# Car.net
KiCad netlist of a schematic drawn in Altium Designer
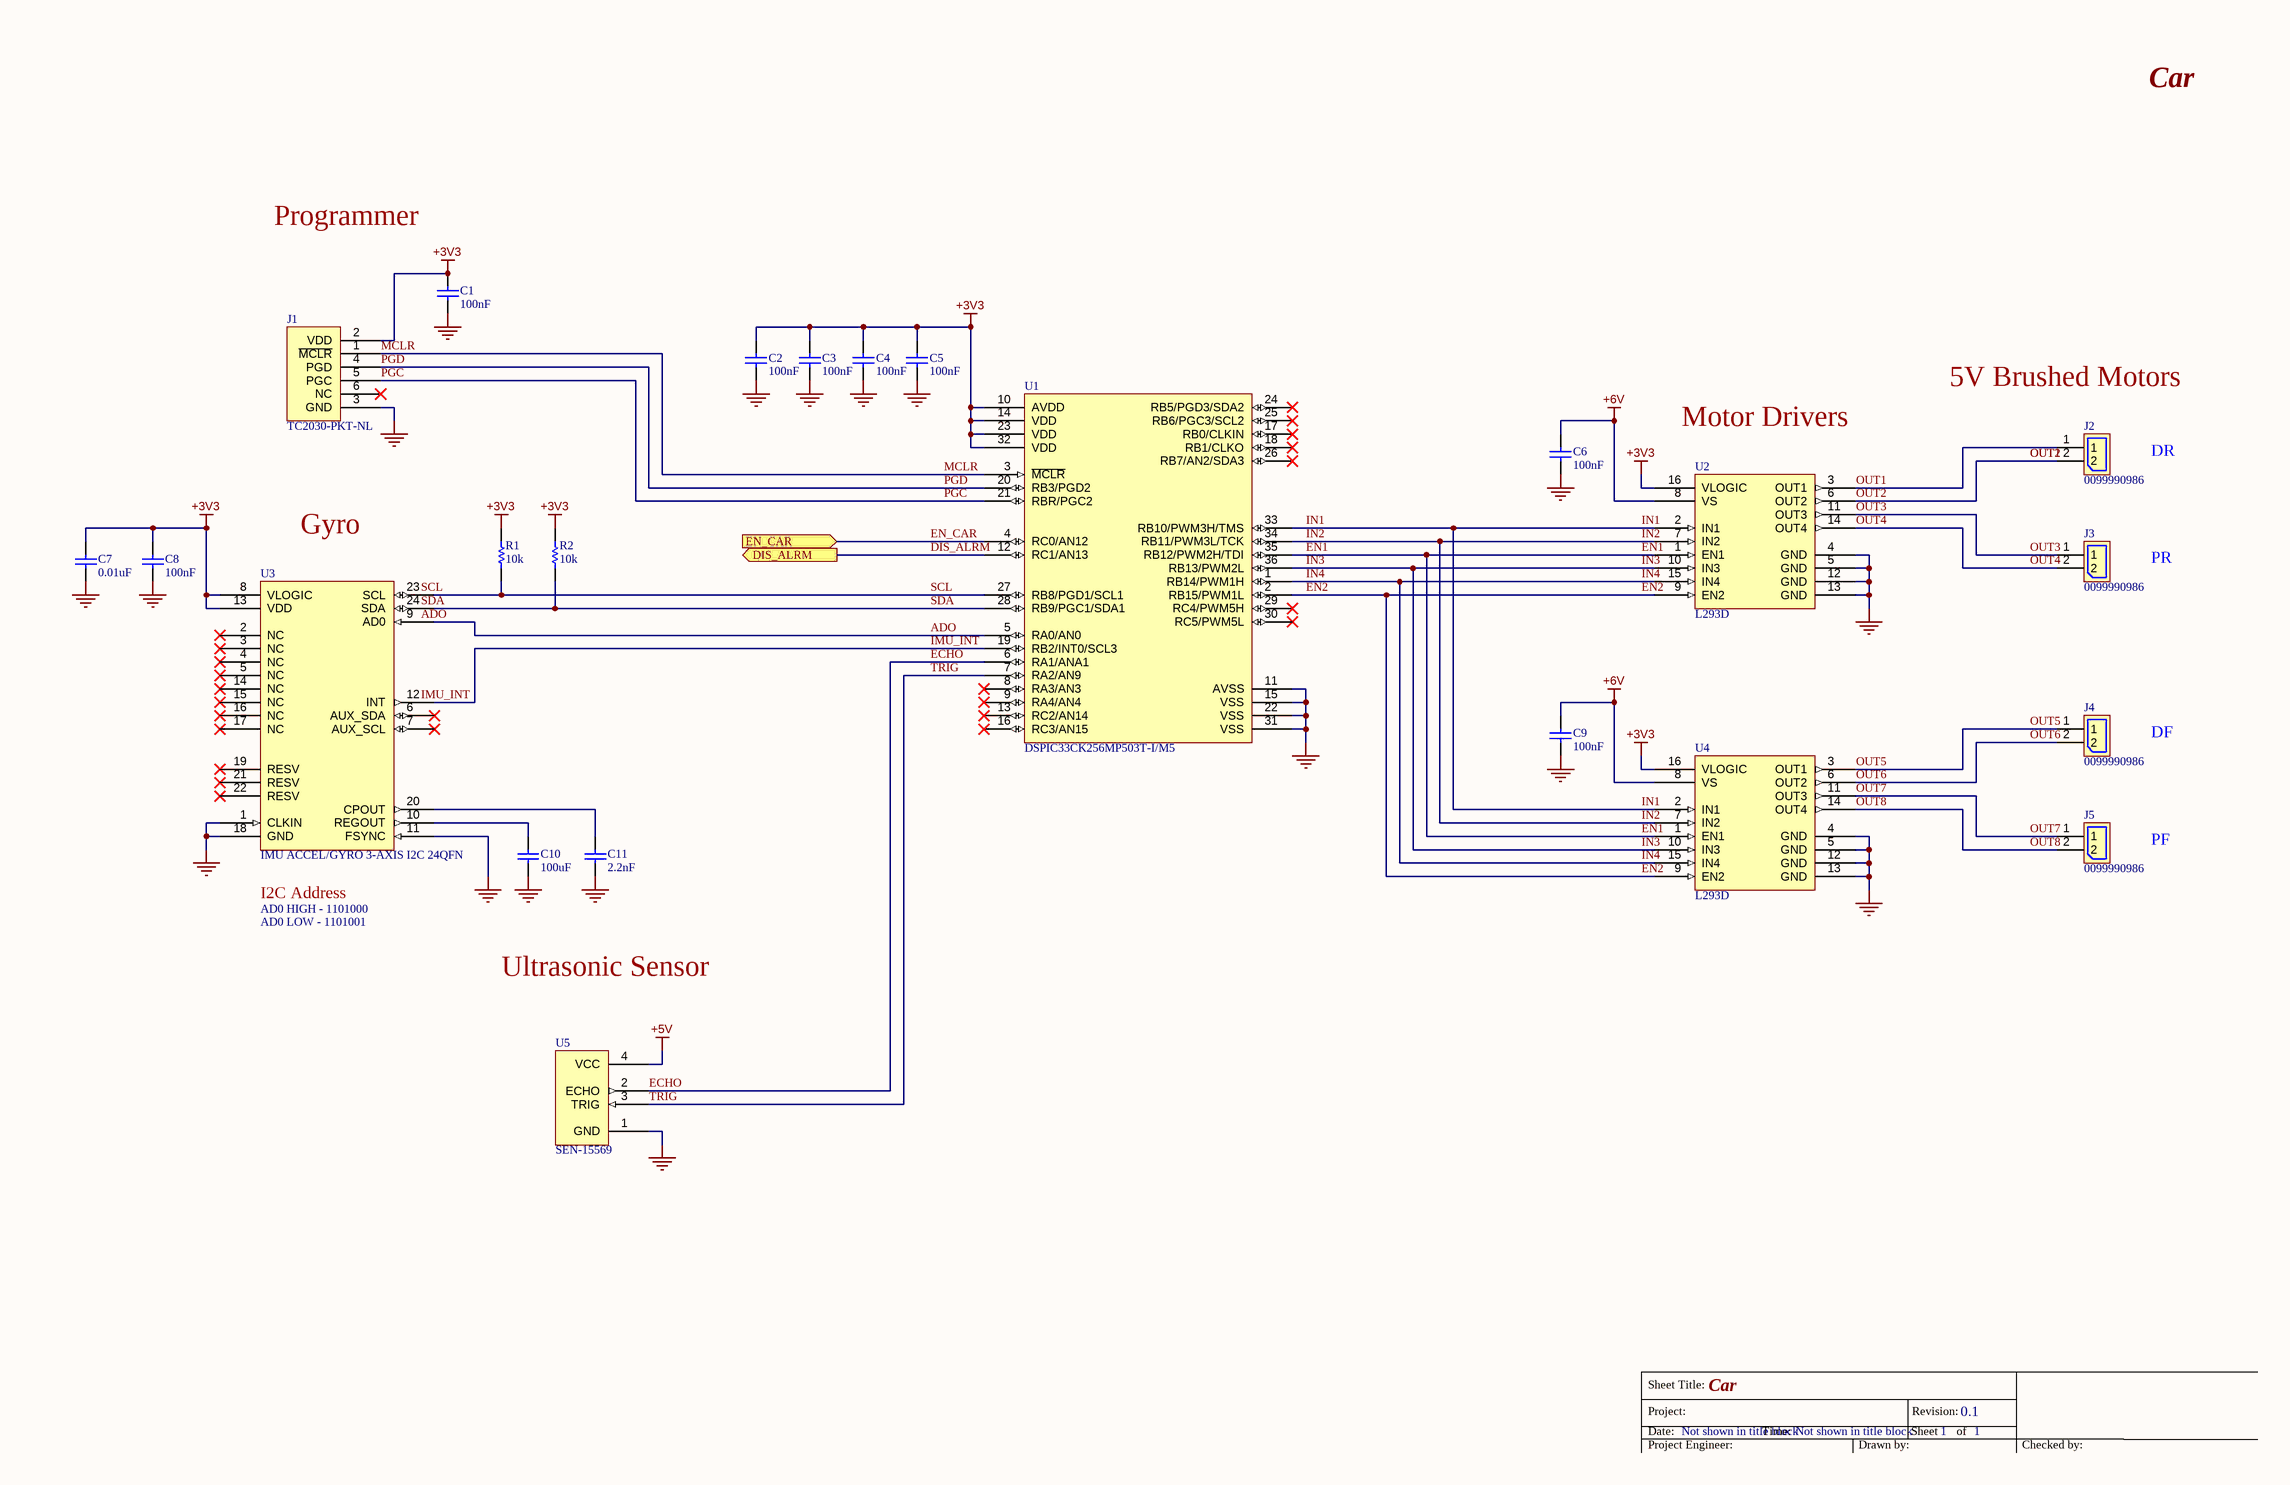
[diagram p0: Car.SchDoc]

(export (version "E")
  (design (tool "Eeschema 10.0.6"))
  (components
    (comp (ref "C1")
      (value "100nF")
      (footprint "C0402")
      (fields (field (name "PART NUMBER") "CL05A104KA5NNNC") (field (name "MANUFACTURER") "Samsung"))
      (libsource (lib "EMRLibrary") (part "EMR_Cap"))
    )
    (comp (ref "C2")
      (value "100nF")
      (footprint "C0402")
      (fields (field (name "PART NUMBER") "CL05A104KA5NNNC") (field (name "MANUFACTURER") "Samsung"))
      (libsource (lib "EMRLibrary") (part "EMR_Cap"))
    )
    (comp (ref "C3")
      (value "100nF")
      (footprint "C0402")
      (fields (field (name "PART NUMBER") "CL05A104KA5NNNC") (field (name "MANUFACTURER") "Samsung"))
      (libsource (lib "EMRLibrary") (part "EMR_Cap"))
    )
    (comp (ref "C4")
      (value "100nF")
      (footprint "C0402")
      (fields (field (name "PART NUMBER") "CL05A104KA5NNNC") (field (name "MANUFACTURER") "Samsung"))
      (libsource (lib "EMRLibrary") (part "EMR_Cap"))
    )
    (comp (ref "C5")
      (value "100nF")
      (footprint "C0402")
      (fields (field (name "PART NUMBER") "CL05A104KA5NNNC") (field (name "MANUFACTURER") "Samsung"))
      (libsource (lib "EMRLibrary") (part "EMR_Cap"))
    )
    (comp (ref "C6")
      (value "100nF")
      (footprint "C0402")
      (fields (field (name "PART NUMBER") "CL05A104KA5NNNC") (field (name "MANUFACTURER") "Samsung"))
      (libsource (lib "EMRLibrary") (part "EMR_Cap"))
    )
    (comp (ref "C7")
      (value "0.01uF")
      (footprint "C0402")
      (fields (field (name "PART NUMBER") "HMK105B7103KVHFE") (field (name "MANUFACTURER") "Taiyo Yuden"))
      (libsource (lib "EMRLibrary") (part "EMR_Cap"))
    )
    (comp (ref "C8")
      (value "100nF")
      (footprint "C0402")
      (description "Cap Ceramic 0.1uF 10V X5R 10% SMD 0402 85C Paper T/R")
      (fields (field (name "PART NUMBER") "CL05A104KP5NNNC") (field (name "MANUFACTURER") "Samsung"))
      (libsource (lib "EMRLibrary") (part "EMR_Cap"))
    )
    (comp (ref "C9")
      (value "100nF")
      (footprint "C0402")
      (fields (field (name "PART NUMBER") "CL05A104KA5NNNC") (field (name "MANUFACTURER") "Samsung"))
      (libsource (lib "EMRLibrary") (part "EMR_Cap"))
    )
    (comp (ref "C10")
      (value "100uF")
      (footprint "C1206")
      (description "Cap Ceramic 100uF 6.3V X5R 20% SMD 1206 85C T/R")
      (fields (field (name "PART NUMBER") "CL31A107MQHNNNE") (field (name "MANUFACTURER") "Samsung"))
      (libsource (lib "EMRLibrary") (part "EMR_Cap"))
    )
    (comp (ref "C11")
      (value "2.2nF")
      (footprint "C0402")
      (description "CAP CER 0402 2.2NF 25V C0G 5%")
      (fields (field (name "PART NUMBER") "C0402C222J3GEC7867") (field (name "MANUFACTURER") "KEMET"))
      (libsource (lib "EMRLibrary") (part "EMR_Cap"))
    )
    (comp (ref "J1")
      (value "TC2030-PKT-NL")
      (footprint "TC2030-PKT-NL")
      (description "Pogo pin cable for PicKit 3")
      (libsource (lib "EMRLibrary") (part "TC2030-PKT-NL"))
    )
    (comp (ref "J2")
      (value "0099990986")
      (footprint "0099990986")
      (fields (field (name "MANUFACTURER") "Molex") (field (name "MANUFACTURER PART NUMBER") "99-99-0986"))
      (libsource (lib "EMRLibrary") (part "0099990986"))
    )
    (comp (ref "J3")
      (value "0099990986")
      (footprint "0099990986")
      (fields (field (name "MANUFACTURER") "Molex") (field (name "MANUFACTURER PART NUMBER") "99-99-0986"))
      (libsource (lib "EMRLibrary") (part "0099990986"))
    )
    (comp (ref "J4")
      (value "0099990986")
      (footprint "0099990986")
      (fields (field (name "MANUFACTURER") "Molex") (field (name "MANUFACTURER PART NUMBER") "99-99-0986"))
      (libsource (lib "EMRLibrary") (part "0099990986"))
    )
    (comp (ref "J5")
      (value "0099990986")
      (footprint "0099990986")
      (fields (field (name "MANUFACTURER") "Molex") (field (name "MANUFACTURER PART NUMBER") "99-99-0986"))
      (libsource (lib "EMRLibrary") (part "0099990986"))
    )
    (comp (ref "R1")
      (value "10k")
      (footprint "RESC1005X04N")
      (description "RES SMD 10K OHM 1% 1/16W 0402")
      (fields (field (name "PART NUMBER") "RC0402FR-0710KL") (field (name "MANUFACTURER") "Yageo"))
      (libsource (lib "EMRLibrary") (part "RC0402"))
    )
    (comp (ref "R2")
      (value "10k")
      (footprint "RESC1005X04N")
      (description "RES SMD 10K OHM 1% 1/16W 0402")
      (fields (field (name "PART NUMBER") "RC0402FR-0710KL") (field (name "MANUFACTURER") "Yageo"))
      (libsource (lib "EMRLibrary") (part "RC0402"))
    )
    (comp (ref "U1")
      (value "DSPIC33CK256MP503T-I/M5")
      (libsource (lib "EMR") (part "DSPIC33CK256MP503T-I/M5"))
    )
    (comp (ref "U2")
      (value "L293D")
      (description "Bipolar Motor Driver - Parallel 16-PowerDIP")
      (libsource (lib "EMR") (part "L293D"))
    )
    (comp (ref "U3")
      (value "IMU ACCEL/GYRO 3-AXIS I2C 24QFN")
      (footprint "QFN50P395X395X95_HS-25N")
      (fields (field (name "PART NUMBER") "MPU-6050") (field (name "MANUFACTURER") "TDK InvenSense"))
      (libsource (lib "EMRLibrary") (part "MPU-6050"))
    )
    (comp (ref "U4")
      (value "L293D")
      (description "Bipolar Motor Driver - Parallel 16-PowerDIP")
      (libsource (lib "EMR") (part "L293D"))
    )
    (comp (ref "U5")
      (value "SEN-15569")
      (footprint "SEN-15569")
      (description "HC-SR04 series Ultrasonic Sensor Evaluation Board")
      (fields (field (name "MANUFACTURER") "SparkFun"))
      (libsource (lib "EMRLibrary") (part "SEN-15569"))
    )
  )
  (nets
    (net (code "1") (name "+3V3") (class "Default")
      (node (ref "C1") (pin "2") (pinfunction "2_2") (pintype "passive"))
      (node (ref "C2") (pin "2") (pinfunction "2_2") (pintype "passive"))
      (node (ref "C3") (pin "2") (pinfunction "2_2") (pintype "passive"))
      (node (ref "C4") (pin "2") (pinfunction "2_2") (pintype "passive"))
      (node (ref "C5") (pin "2") (pinfunction "2_2") (pintype "passive"))
      (node (ref "C7") (pin "2") (pinfunction "2_2") (pintype "passive"))
      (node (ref "C8") (pin "2") (pinfunction "2_2") (pintype "passive"))
      (node (ref "J1") (pin "2") (pinfunction "VDD_2") (pintype "passive"))
      (node (ref "R1") (pin "2") (pinfunction "2_2") (pintype "passive"))
      (node (ref "R2") (pin "2") (pinfunction "2_2") (pintype "passive"))
      (node (ref "U1") (pin "10") (pinfunction "AVDD_10") (pintype "power_in"))
      (node (ref "U1") (pin "14") (pinfunction "VDD_14") (pintype "power_in"))
      (node (ref "U1") (pin "23") (pinfunction "VDD_23") (pintype "power_in"))
      (node (ref "U1") (pin "32") (pinfunction "VDD_32") (pintype "power_in"))
      (node (ref "U2") (pin "16") (pinfunction "VLOGIC_16") (pintype "power_in"))
      (node (ref "U3") (pin "13") (pinfunction "VDD_13") (pintype "power_in"))
      (node (ref "U3") (pin "8") (pinfunction "VLOGIC_8") (pintype "power_in"))
      (node (ref "U4") (pin "16") (pinfunction "VLOGIC_16") (pintype "power_in"))
    )
    (net (code "2") (name "+5V") (class "Default")
      (node (ref "U5") (pin "4") (pinfunction "VCC_4") (pintype "power_in"))
    )
    (net (code "3") (name "+6V") (class "Default")
      (node (ref "C6") (pin "2") (pinfunction "2_2") (pintype "passive"))
      (node (ref "C9") (pin "2") (pinfunction "2_2") (pintype "passive"))
      (node (ref "U2") (pin "8") (pinfunction "VS_8") (pintype "power_in"))
      (node (ref "U4") (pin "8") (pinfunction "VS_8") (pintype "power_in"))
    )
    (net (code "4") (name "/ADO") (class "Default")
      (node (ref "U1") (pin "5") (pinfunction "RA0/AN0_5") (pintype "bidirectional"))
      (node (ref "U3") (pin "9") (pinfunction "AD0_9") (pintype "input"))
    )
    (net (code "5") (name "/DIS_ALRM") (class "Default")
      (node (ref "U1") (pin "12") (pinfunction "RC1/AN13_12") (pintype "bidirectional"))
    )
    (net (code "6") (name "/ECHO") (class "Default")
      (node (ref "U1") (pin "6") (pinfunction "RA1/ANA1_6") (pintype "bidirectional"))
      (node (ref "U5") (pin "2") (pinfunction "ECHO_2") (pintype "output"))
    )
    (net (code "7") (name "/EN1") (class "Default")
      (node (ref "U1") (pin "35") (pinfunction "RB12/PWM2H/TDI_35") (pintype "bidirectional"))
      (node (ref "U2") (pin "1") (pinfunction "EN1_1") (pintype "input"))
      (node (ref "U4") (pin "1") (pinfunction "EN1_1") (pintype "input"))
    )
    (net (code "8") (name "/EN2") (class "Default")
      (node (ref "U1") (pin "2") (pinfunction "RB15/PWM1L_2") (pintype "bidirectional"))
      (node (ref "U2") (pin "9") (pinfunction "EN2_9") (pintype "input"))
      (node (ref "U4") (pin "9") (pinfunction "EN2_9") (pintype "input"))
    )
    (net (code "9") (name "/EN_CAR") (class "Default")
      (node (ref "U1") (pin "4") (pinfunction "RC0/AN12_4") (pintype "bidirectional"))
    )
    (net (code "10") (name "/IMU_INT") (class "Default")
      (node (ref "U1") (pin "19") (pinfunction "RB2/INT0/SCL3_19") (pintype "bidirectional"))
      (node (ref "U3") (pin "12") (pinfunction "INT_12") (pintype "output"))
    )
    (net (code "11") (name "/IN1") (class "Default")
      (node (ref "U1") (pin "33") (pinfunction "RB10/PWM3H/TMS_33") (pintype "bidirectional"))
      (node (ref "U2") (pin "2") (pinfunction "IN1_2") (pintype "input"))
      (node (ref "U4") (pin "2") (pinfunction "IN1_2") (pintype "input"))
    )
    (net (code "12") (name "/IN2") (class "Default")
      (node (ref "U1") (pin "34") (pinfunction "RB11/PWM3L/TCK_34") (pintype "bidirectional"))
      (node (ref "U2") (pin "7") (pinfunction "IN2_7") (pintype "input"))
      (node (ref "U4") (pin "7") (pinfunction "IN2_7") (pintype "input"))
    )
    (net (code "13") (name "/IN3") (class "Default")
      (node (ref "U1") (pin "36") (pinfunction "RB13/PWM2L_36") (pintype "bidirectional"))
      (node (ref "U2") (pin "10") (pinfunction "IN3_10") (pintype "input"))
      (node (ref "U4") (pin "10") (pinfunction "IN3_10") (pintype "input"))
    )
    (net (code "14") (name "/IN4") (class "Default")
      (node (ref "U1") (pin "1") (pinfunction "RB14/PWM1H_1") (pintype "bidirectional"))
      (node (ref "U2") (pin "15") (pinfunction "IN4_15") (pintype "input"))
      (node (ref "U4") (pin "15") (pinfunction "IN4_15") (pintype "input"))
    )
    (net (code "15") (name "/MCLR") (class "Default")
      (node (ref "J1") (pin "1") (pinfunction "~{MCLR}_1") (pintype "passive"))
      (node (ref "U1") (pin "3") (pinfunction "~{MCLR}_3") (pintype "input"))
    )
    (net (code "16") (name "/OUT1") (class "Default")
      (node (ref "J2") (pin "1") (pinfunction "1_1") (pintype "passive"))
      (node (ref "J2") (pin "2") (pinfunction "2_2") (pintype "passive"))
      (node (ref "U2") (pin "3") (pinfunction "OUT1_3") (pintype "output"))
      (node (ref "U2") (pin "6") (pinfunction "OUT2_6") (pintype "output"))
    )
    (net (code "17") (name "/OUT3") (class "Default")
      (node (ref "J3") (pin "1") (pinfunction "1_1") (pintype "passive"))
      (node (ref "U2") (pin "11") (pinfunction "OUT3_11") (pintype "output"))
    )
    (net (code "18") (name "/OUT4") (class "Default")
      (node (ref "J3") (pin "2") (pinfunction "2_2") (pintype "passive"))
      (node (ref "U2") (pin "14") (pinfunction "OUT4_14") (pintype "output"))
    )
    (net (code "19") (name "/OUT5") (class "Default")
      (node (ref "J4") (pin "1") (pinfunction "1_1") (pintype "passive"))
      (node (ref "U4") (pin "3") (pinfunction "OUT1_3") (pintype "output"))
    )
    (net (code "20") (name "/OUT6") (class "Default")
      (node (ref "J4") (pin "2") (pinfunction "2_2") (pintype "passive"))
      (node (ref "U4") (pin "6") (pinfunction "OUT2_6") (pintype "output"))
    )
    (net (code "21") (name "/OUT7") (class "Default")
      (node (ref "J5") (pin "1") (pinfunction "1_1") (pintype "passive"))
      (node (ref "U4") (pin "11") (pinfunction "OUT3_11") (pintype "output"))
    )
    (net (code "22") (name "/OUT8") (class "Default")
      (node (ref "J5") (pin "2") (pinfunction "2_2") (pintype "passive"))
      (node (ref "U4") (pin "14") (pinfunction "OUT4_14") (pintype "output"))
    )
    (net (code "23") (name "/PGC") (class "Default")
      (node (ref "J1") (pin "5") (pinfunction "PGC_5") (pintype "passive"))
      (node (ref "U1") (pin "21") (pinfunction "RBR/PGC2_21") (pintype "bidirectional"))
    )
    (net (code "24") (name "/PGD") (class "Default")
      (node (ref "J1") (pin "4") (pinfunction "PGD_4") (pintype "passive"))
      (node (ref "U1") (pin "20") (pinfunction "RB3/PGD2_20") (pintype "bidirectional"))
    )
    (net (code "25") (name "/SCL") (class "Default")
      (node (ref "R1") (pin "1") (pinfunction "1_1") (pintype "passive"))
      (node (ref "U1") (pin "27") (pinfunction "RB8/PGD1/SCL1_27") (pintype "bidirectional"))
      (node (ref "U3") (pin "23") (pinfunction "SCL_23") (pintype "bidirectional"))
    )
    (net (code "26") (name "/SDA") (class "Default")
      (node (ref "R2") (pin "1") (pinfunction "1_1") (pintype "passive"))
      (node (ref "U1") (pin "28") (pinfunction "RB9/PGC1/SDA1_28") (pintype "bidirectional"))
      (node (ref "U3") (pin "24") (pinfunction "SDA_24") (pintype "bidirectional"))
    )
    (net (code "27") (name "/TRIG") (class "Default")
      (node (ref "U1") (pin "7") (pinfunction "RA2/AN9_7") (pintype "bidirectional"))
      (node (ref "U5") (pin "3") (pinfunction "TRIG_3") (pintype "input"))
    )
    (net (code "28") (name "GND") (class "Default")
      (node (ref "C1") (pin "1") (pinfunction "1_1") (pintype "passive"))
      (node (ref "C10") (pin "1") (pinfunction "1_1") (pintype "passive"))
      (node (ref "C11") (pin "1") (pinfunction "1_1") (pintype "passive"))
      (node (ref "C2") (pin "1") (pinfunction "1_1") (pintype "passive"))
      (node (ref "C3") (pin "1") (pinfunction "1_1") (pintype "passive"))
      (node (ref "C4") (pin "1") (pinfunction "1_1") (pintype "passive"))
      (node (ref "C5") (pin "1") (pinfunction "1_1") (pintype "passive"))
      (node (ref "C6") (pin "1") (pinfunction "1_1") (pintype "passive"))
      (node (ref "C7") (pin "1") (pinfunction "1_1") (pintype "passive"))
      (node (ref "C8") (pin "1") (pinfunction "1_1") (pintype "passive"))
      (node (ref "C9") (pin "1") (pinfunction "1_1") (pintype "passive"))
      (node (ref "J1") (pin "3") (pinfunction "GND_3") (pintype "passive"))
      (node (ref "U1") (pin "11") (pinfunction "AVSS_11") (pintype "power_in"))
      (node (ref "U1") (pin "15") (pinfunction "VSS_15") (pintype "power_in"))
      (node (ref "U1") (pin "22") (pinfunction "VSS_22") (pintype "power_in"))
      (node (ref "U1") (pin "31") (pinfunction "VSS_31") (pintype "power_in"))
      (node (ref "U2") (pin "12") (pinfunction "GND_12") (pintype "power_in"))
      (node (ref "U2") (pin "13") (pinfunction "GND_13") (pintype "power_in"))
      (node (ref "U2") (pin "4") (pinfunction "GND_4") (pintype "power_in"))
      (node (ref "U2") (pin "5") (pinfunction "GND_5") (pintype "power_in"))
      (node (ref "U3") (pin "1") (pinfunction "CLKIN_1") (pintype "input"))
      (node (ref "U3") (pin "11") (pinfunction "FSYNC_11") (pintype "input"))
      (node (ref "U3") (pin "18") (pinfunction "GND_18") (pintype "power_in"))
      (node (ref "U4") (pin "12") (pinfunction "GND_12") (pintype "power_in"))
      (node (ref "U4") (pin "13") (pinfunction "GND_13") (pintype "power_in"))
      (node (ref "U4") (pin "4") (pinfunction "GND_4") (pintype "power_in"))
      (node (ref "U4") (pin "5") (pinfunction "GND_5") (pintype "power_in"))
      (node (ref "U5") (pin "1") (pinfunction "GND_1") (pintype "power_in"))
    )
    (net (code "29") (name "Net-(U3-CPOUT)") (class "Default")
      (node (ref "C11") (pin "2") (pinfunction "2_2") (pintype "passive"))
      (node (ref "U3") (pin "20") (pinfunction "CPOUT_20") (pintype "output"))
    )
    (net (code "30") (name "Net-(U3-REGOUT)") (class "Default")
      (node (ref "C10") (pin "2") (pinfunction "2_2") (pintype "passive"))
      (node (ref "U3") (pin "10") (pinfunction "REGOUT_10") (pintype "output"))
    )
    (net (code "31") (name "unconnected-(J1-NC-Pad6)") (class "Default")
      (node (ref "J1") (pin "6") (pinfunction "NC_6") (pintype "passive+no_connect"))
    )
    (net (code "32") (name "unconnected-(U1-RA3{slash}AN3-Pad8)") (class "Default")
      (node (ref "U1") (pin "8") (pinfunction "RA3/AN3_8") (pintype "bidirectional+no_connect"))
    )
    (net (code "33") (name "unconnected-(U1-RA4{slash}AN4-Pad9)") (class "Default")
      (node (ref "U1") (pin "9") (pinfunction "RA4/AN4_9") (pintype "bidirectional+no_connect"))
    )
    (net (code "34") (name "unconnected-(U1-RB0{slash}CLKIN-Pad17)") (class "Default")
      (node (ref "U1") (pin "17") (pinfunction "RB0/CLKIN_17") (pintype "bidirectional+no_connect"))
    )
    (net (code "35") (name "unconnected-(U1-RB1{slash}CLKO-Pad18)") (class "Default")
      (node (ref "U1") (pin "18") (pinfunction "RB1/CLKO_18") (pintype "bidirectional+no_connect"))
    )
    (net (code "36") (name "unconnected-(U1-RB5{slash}PGD3{slash}SDA2-Pad24)") (class "Default")
      (node (ref "U1") (pin "24") (pinfunction "RB5/PGD3/SDA2_24") (pintype "bidirectional+no_connect"))
    )
    (net (code "37") (name "unconnected-(U1-RB6{slash}PGC3{slash}SCL2-Pad25)") (class "Default")
      (node (ref "U1") (pin "25") (pinfunction "RB6/PGC3/SCL2_25") (pintype "bidirectional+no_connect"))
    )
    (net (code "38") (name "unconnected-(U1-RB7{slash}AN2{slash}SDA3-Pad26)") (class "Default")
      (node (ref "U1") (pin "26") (pinfunction "RB7/AN2/SDA3_26") (pintype "bidirectional+no_connect"))
    )
    (net (code "39") (name "unconnected-(U1-RC2{slash}AN14-Pad13)") (class "Default")
      (node (ref "U1") (pin "13") (pinfunction "RC2/AN14_13") (pintype "bidirectional+no_connect"))
    )
    (net (code "40") (name "unconnected-(U1-RC3{slash}AN15-Pad16)") (class "Default")
      (node (ref "U1") (pin "16") (pinfunction "RC3/AN15_16") (pintype "bidirectional+no_connect"))
    )
    (net (code "41") (name "unconnected-(U1-RC4{slash}PWM5H-Pad29)") (class "Default")
      (node (ref "U1") (pin "29") (pinfunction "RC4/PWM5H_29") (pintype "bidirectional+no_connect"))
    )
    (net (code "42") (name "unconnected-(U1-RC5{slash}PWM5L-Pad30)") (class "Default")
      (node (ref "U1") (pin "30") (pinfunction "RC5/PWM5L_30") (pintype "bidirectional+no_connect"))
    )
    (net (code "43") (name "unconnected-(U3-AUX_SCL-Pad7)") (class "Default")
      (node (ref "U3") (pin "7") (pinfunction "AUX_SCL_7") (pintype "bidirectional+no_connect"))
    )
    (net (code "44") (name "unconnected-(U3-AUX_SDA-Pad6)") (class "Default")
      (node (ref "U3") (pin "6") (pinfunction "AUX_SDA_6") (pintype "bidirectional+no_connect"))
    )
    (net (code "45") (name "unconnected-(U3-NC-Pad2)") (class "Default")
      (node (ref "U3") (pin "2") (pinfunction "NC_2") (pintype "passive+no_connect"))
    )
    (net (code "46") (name "unconnected-(U3-NC-Pad3)") (class "Default")
      (node (ref "U3") (pin "3") (pinfunction "NC_3") (pintype "passive+no_connect"))
    )
    (net (code "47") (name "unconnected-(U3-NC-Pad4)") (class "Default")
      (node (ref "U3") (pin "4") (pinfunction "NC_4") (pintype "passive+no_connect"))
    )
    (net (code "48") (name "unconnected-(U3-NC-Pad5)") (class "Default")
      (node (ref "U3") (pin "5") (pinfunction "NC_5") (pintype "passive+no_connect"))
    )
    (net (code "49") (name "unconnected-(U3-NC-Pad14)") (class "Default")
      (node (ref "U3") (pin "14") (pinfunction "NC_14") (pintype "passive+no_connect"))
    )
    (net (code "50") (name "unconnected-(U3-NC-Pad15)") (class "Default")
      (node (ref "U3") (pin "15") (pinfunction "NC_15") (pintype "passive+no_connect"))
    )
    (net (code "51") (name "unconnected-(U3-NC-Pad16)") (class "Default")
      (node (ref "U3") (pin "16") (pinfunction "NC_16") (pintype "passive+no_connect"))
    )
    (net (code "52") (name "unconnected-(U3-NC-Pad17)") (class "Default")
      (node (ref "U3") (pin "17") (pinfunction "NC_17") (pintype "passive+no_connect"))
    )
    (net (code "53") (name "unconnected-(U3-RESV-Pad19)") (class "Default")
      (node (ref "U3") (pin "19") (pinfunction "RESV_19") (pintype "passive+no_connect"))
    )
    (net (code "54") (name "unconnected-(U3-RESV-Pad21)") (class "Default")
      (node (ref "U3") (pin "21") (pinfunction "RESV_21") (pintype "passive+no_connect"))
    )
    (net (code "55") (name "unconnected-(U3-RESV-Pad22)") (class "Default")
      (node (ref "U3") (pin "22") (pinfunction "RESV_22") (pintype "passive+no_connect"))
    )
  )
)
